# McPiFace-Pi4-MiniOled-V2.net
KiCad netlist of a schematic drawn in EAGLE
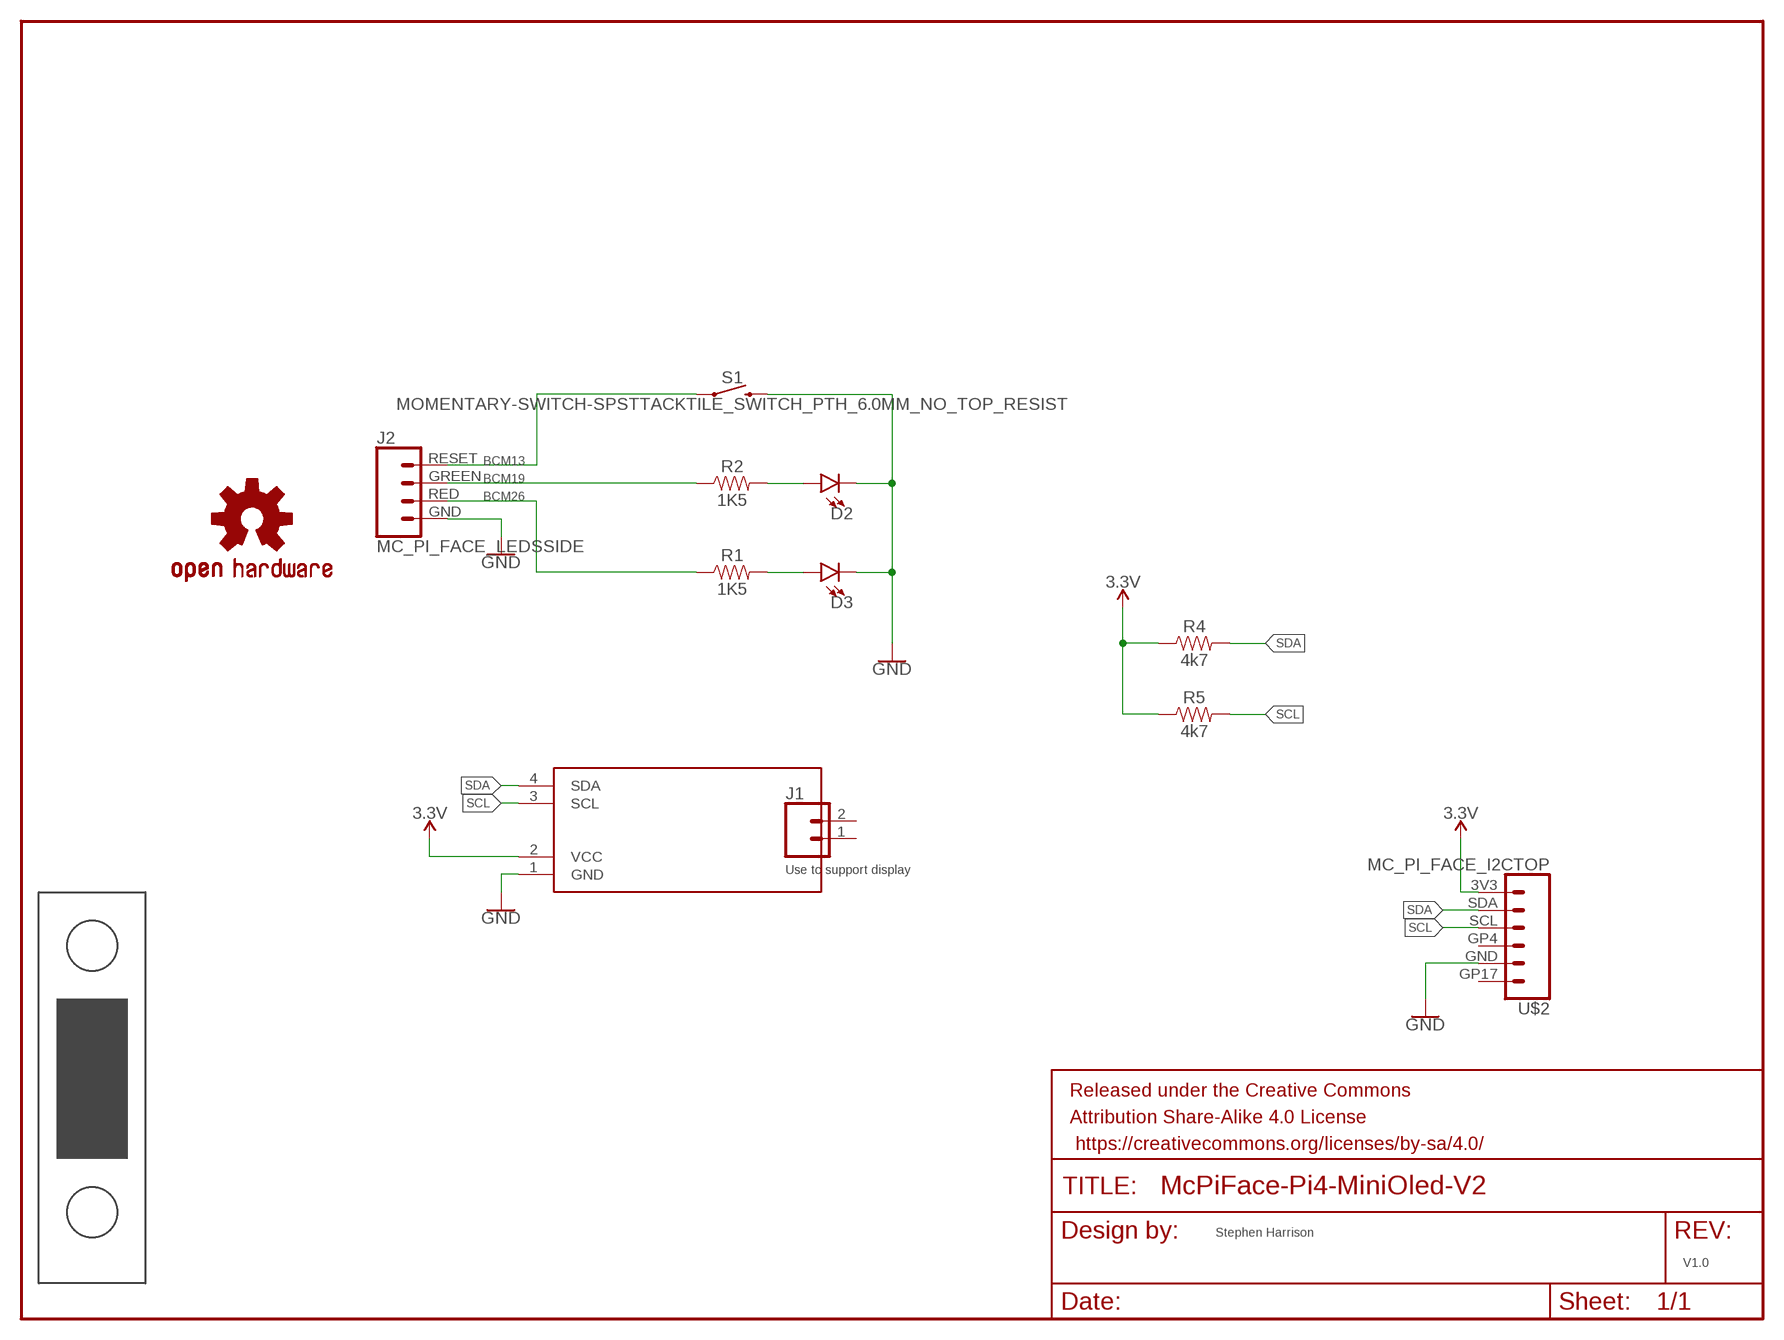
[diagram p0: schematic, sheet 1]

(export (version "E")
  (design (tool "Eeschema 10.0.6"))
  (components
    (comp (ref "D2")
      (value "LEDLED-1206-BOTTOM-2.0MM-GREEN")
      (footprint "eagle-import:LED-1206-BOTTOM-2.0MM")
      (libsource (lib "eagle-import") (part "LEDLED-1206-BOTTOM-2.0MM-GREEN"))
    )
    (comp (ref "D3")
      (value "LEDLED-1206-BOTTOM-2.0MM-RED")
      (footprint "eagle-import:LED-1206-BOTTOM-2.0MM")
      (libsource (lib "eagle-import") (part "LEDLED-1206-BOTTOM-2.0MM-RED"))
    )
    (comp (ref "DISPLAY")
      (value "DISPLAY0.91_INCH_DISPLAY")
      (footprint "eagle-import:I2C_DISPLAY_0.91_INCH")
      (libsource (lib "eagle-import") (part "DISPLAY0.91_INCH_DISPLAY"))
    )
    (comp (ref "FRAME1")
      (value "FRAME-LETTER")
      (footprint "eagle-import:CREATIVE_COMMONS")
      (libsource (lib "eagle-import") (part "FRAME-LETTER"))
    )
    (comp (ref "J1")
      (value "CONN_021X02_NO_SILK")
      (footprint "eagle-import:1X02_NO_SILK")
      (libsource (lib "eagle-import") (part "CONN_021X02_NO_SILK"))
    )
    (comp (ref "J2")
      (value "MC_PI_FACE_LEDSSIDE")
      (footprint "eagle-import:JST-4-SH-1.0MM-SIDE")
      (fields (field (name "MFG") "SM04B-SRSS-TB(LF)(SN)"))
      (libsource (lib "eagle-import") (part "MC_PI_FACE_LEDSSIDE"))
    )
    (comp (ref "LOGO1")
      (value "OSHW-LOGOL")
      (footprint "eagle-import:OSHW-LOGO-L")
      (libsource (lib "eagle-import") (part "OSHW-LOGOL"))
    )
    (comp (ref "R1")
      (value "1K5")
      (footprint "eagle-import:0805")
      (libsource (lib "eagle-import") (part "RESISTOR0805"))
    )
    (comp (ref "R2")
      (value "1K5")
      (footprint "eagle-import:0805")
      (libsource (lib "eagle-import") (part "RESISTOR0805"))
    )
    (comp (ref "R4")
      (value "4k7")
      (footprint "eagle-import:0805")
      (libsource (lib "eagle-import") (part "RESISTOR0805"))
    )
    (comp (ref "R5")
      (value "4k7")
      (footprint "eagle-import:0805")
      (libsource (lib "eagle-import") (part "RESISTOR0805"))
    )
    (comp (ref "S1")
      (value "MOMENTARY-SWITCH-SPSTTACKTILE_SWITCH_PTH_6.0MM_NO_TOP_RESIST")
      (footprint "eagle-import:TACTILE_SWITCH_PTH_6.0MM_NO_TOP_RESIST")
      (libsource (lib "eagle-import") (part "MOMENTARY-SWITCH-SPSTTACKTILE_SWITCH_PTH_6.0MM_NO_TOP_RESIST"))
    )
    (comp (ref "U$1")
      (value "MC_PI_4_FACE_PANEL")
      (footprint "eagle-import:MC_PI_4_FACE")
      (libsource (lib "eagle-import") (part "MC_PI_4_FACE_PANEL"))
    )
    (comp (ref "U$2")
      (value "MC_PI_FACE_I2CTOP")
      (footprint "eagle-import:JST-6-SH-1.0MM-TOP")
      (libsource (lib "eagle-import") (part "MC_PI_FACE_I2CTOP"))
    )
  )
  (nets
    (net (code "1") (name "/BCM13") (class "Default")
      (node (ref "J2") (pin "RESET") (pinfunction "RESET_RESET") (pintype "passive"))
      (node (ref "S1") (pin "1") (pinfunction "1_1") (pintype "passive"))
    )
    (net (code "2") (name "/BCM19") (class "Default")
      (node (ref "J2") (pin "GREEN") (pinfunction "GREEN_GREEN") (pintype "passive"))
      (node (ref "R2") (pin "1") (pinfunction "1_1") (pintype "passive"))
    )
    (net (code "3") (name "/BCM26") (class "Default")
      (node (ref "J2") (pin "RED") (pinfunction "RED_RED") (pintype "passive"))
      (node (ref "R1") (pin "1") (pinfunction "1_1") (pintype "passive"))
    )
    (net (code "4") (name "3.3V") (class "Default")
      (node (ref "DISPLAY") (pin "2") (pinfunction "VCC_2") (pintype "power_in"))
      (node (ref "R4") (pin "1") (pinfunction "1_1") (pintype "passive"))
      (node (ref "R5") (pin "1") (pinfunction "1_1") (pintype "passive"))
      (node (ref "U$2") (pin "3V3") (pinfunction "3V3_3V3") (pintype "power_in"))
    )
    (net (code "5") (name "GND") (class "Default")
      (node (ref "D2") (pin "C") (pinfunction "C_C") (pintype "passive"))
      (node (ref "D3") (pin "C") (pinfunction "C_C") (pintype "passive"))
      (node (ref "DISPLAY") (pin "1") (pinfunction "GND_1") (pintype "power_in"))
      (node (ref "J2") (pin "GND") (pinfunction "GND_GND") (pintype "power_in"))
      (node (ref "S1") (pin "3") (pinfunction "2_3") (pintype "passive"))
      (node (ref "U$2") (pin "GND") (pinfunction "GND_GND") (pintype "power_in"))
    )
    (net (code "6") (name "Net-(D2-PadA)") (class "Default")
      (node (ref "D2") (pin "A") (pinfunction "A_A") (pintype "passive"))
      (node (ref "R2") (pin "2") (pinfunction "2_2") (pintype "passive"))
    )
    (net (code "7") (name "Net-(D3-PadA)") (class "Default")
      (node (ref "D3") (pin "A") (pinfunction "A_A") (pintype "passive"))
      (node (ref "R1") (pin "2") (pinfunction "2_2") (pintype "passive"))
    )
    (net (code "8") (name "SCL") (class "Default")
      (node (ref "DISPLAY") (pin "3") (pinfunction "SCL_3") (pintype "bidirectional"))
      (node (ref "R5") (pin "2") (pinfunction "2_2") (pintype "passive"))
      (node (ref "U$2") (pin "SCL") (pinfunction "SCL_SCL") (pintype "bidirectional"))
    )
    (net (code "9") (name "SDA") (class "Default")
      (node (ref "DISPLAY") (pin "4") (pinfunction "SDA_4") (pintype "bidirectional"))
      (node (ref "R4") (pin "2") (pinfunction "2_2") (pintype "passive"))
      (node (ref "U$2") (pin "SDA") (pinfunction "SDA_SDA") (pintype "bidirectional"))
    )
    (net (code "10") (name "unconnected-(J1-Pad1)") (class "Default")
      (node (ref "J1") (pin "1") (pinfunction "1_1") (pintype "passive"))
    )
    (net (code "11") (name "unconnected-(J1-Pad2)") (class "Default")
      (node (ref "J1") (pin "2") (pinfunction "2_2") (pintype "passive"))
    )
    (net (code "12") (name "unconnected-(U$2-PadGP4)") (class "Default")
      (node (ref "U$2") (pin "GP4") (pinfunction "GP4_GP4") (pintype "bidirectional"))
    )
    (net (code "13") (name "unconnected-(U$2-PadGP17)") (class "Default")
      (node (ref "U$2") (pin "GP17") (pinfunction "GP17_GP17") (pintype "bidirectional"))
    )
  )
)
